# akcel_onlyboard.net
KiCad netlist of a schematic drawn in EAGLE
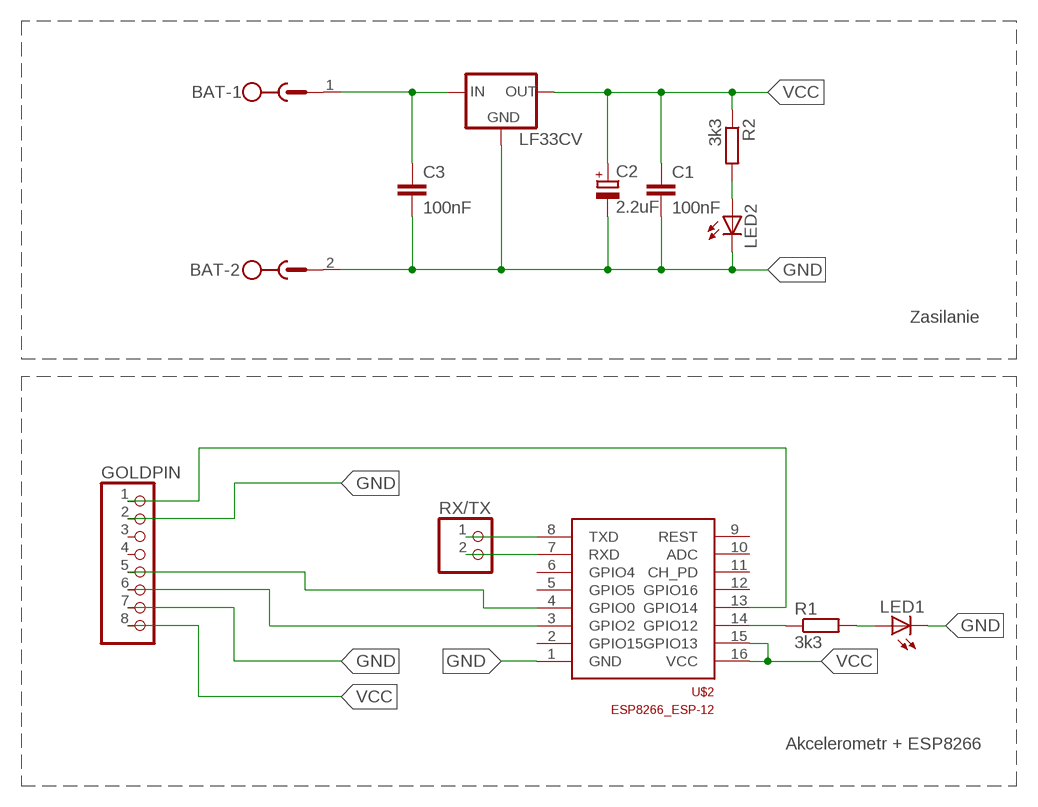
[diagram p0: schematic, sheet 1]

(export (version "E")
  (design (tool "Eeschema 10.0.6"))
  (components
    (comp (ref "BAT")
      (value "MSTBV2")
      (footprint "eagle-import:MSTBV2")
      (libsource (lib "eagle-import") (part "MSTBV2"))
    )
    (comp (ref "C1")
      (value "100nF")
      (footprint "eagle-import:C0805K")
      (libsource (lib "eagle-import") (part "C-EUC0805K"))
    )
    (comp (ref "C2")
      (value "2.2uF")
      (footprint "eagle-import:153CLV-0405")
      (libsource (lib "eagle-import") (part "CPOL-EU153CLV-0405"))
    )
    (comp (ref "C3")
      (value "100nF")
      (footprint "eagle-import:C0805K")
      (libsource (lib "eagle-import") (part "C-EUC0805K"))
    )
    (comp (ref "GOLDPIN")
      (value "PINHD-1X8")
      (footprint "eagle-import:1X08")
      (libsource (lib "eagle-import") (part "PINHD-1X8"))
    )
    (comp (ref "LED1")
      (value "LED3MM")
      (footprint "eagle-import:LED3MM")
      (libsource (lib "eagle-import") (part "LED3MM"))
    )
    (comp (ref "LED2")
      (value "LED3MM")
      (footprint "eagle-import:LED3MM")
      (libsource (lib "eagle-import") (part "LED3MM"))
    )
    (comp (ref "LF33CV")
      (value "LM1117TO252")
      (footprint "eagle-import:TO252")
      (libsource (lib "eagle-import") (part "LM1117TO252"))
    )
    (comp (ref "R1")
      (value "3k3")
      (footprint "eagle-import:M0805")
      (libsource (lib "eagle-import") (part "R-EU_M0805"))
    )
    (comp (ref "R2")
      (value "3k3")
      (footprint "eagle-import:M0805")
      (libsource (lib "eagle-import") (part "R-EU_M0805"))
    )
    (comp (ref "RX/TX")
      (value "PINHD-1X2")
      (footprint "eagle-import:1X02")
      (libsource (lib "eagle-import") (part "PINHD-1X2"))
    )
    (comp (ref "U$2")
      (value "ESP8266_ESP-12")
      (footprint "eagle-import:ESP8266-ESP12")
      (libsource (lib "eagle-import") (part "ESP8266_ESP-12"))
    )
  )
  (nets
    (net (code "1") (name "GND") (class "Default")
      (node (ref "BAT") (pin "2") (pinfunction "SK_2") (pintype "passive"))
      (node (ref "C1") (pin "2") (pinfunction "2_2") (pintype "passive"))
      (node (ref "C2") (pin "-") (pinfunction "-_-") (pintype "passive"))
      (node (ref "C3") (pin "2") (pinfunction "2_2") (pintype "passive"))
      (node (ref "GOLDPIN") (pin "2") (pinfunction "2_2") (pintype "passive"))
      (node (ref "GOLDPIN") (pin "7") (pinfunction "7_7") (pintype "passive"))
      (node (ref "LED1") (pin "K") (pinfunction "C_K") (pintype "passive"))
      (node (ref "LED2") (pin "K") (pinfunction "C_K") (pintype "passive"))
      (node (ref "LF33CV") (pin "3") (pinfunction "GND_3") (pintype "input"))
      (node (ref "U$2") (pin "1") (pinfunction "GND_1") (pintype "bidirectional"))
    )
    (net (code "2") (name "Net-(BATA-SK)") (class "Default")
      (node (ref "BAT") (pin "1") (pinfunction "SK_1") (pintype "passive"))
      (node (ref "C3") (pin "1") (pinfunction "1_1") (pintype "passive"))
      (node (ref "LF33CV") (pin "1") (pinfunction "IN_1") (pintype "input"))
    )
    (net (code "3") (name "Net-(LED1-PadA)") (class "Default")
      (node (ref "LED1") (pin "A") (pinfunction "A_A") (pintype "passive"))
      (node (ref "R1") (pin "2") (pinfunction "2_2") (pintype "passive"))
    )
    (net (code "4") (name "Net-(LED2-PadA)") (class "Default")
      (node (ref "LED2") (pin "A") (pinfunction "A_A") (pintype "passive"))
      (node (ref "R2") (pin "2") (pinfunction "2_2") (pintype "passive"))
    )
    (net (code "5") (name "Net-(U$2-GPIO0)") (class "Default")
      (node (ref "GOLDPIN") (pin "5") (pinfunction "5_5") (pintype "passive"))
      (node (ref "U$2") (pin "4") (pinfunction "GPIO0_4") (pintype "bidirectional"))
    )
    (net (code "6") (name "Net-(U$2-GPIO2)") (class "Default")
      (node (ref "GOLDPIN") (pin "6") (pinfunction "6_6") (pintype "passive"))
      (node (ref "U$2") (pin "3") (pinfunction "GPIO2_3") (pintype "bidirectional"))
    )
    (net (code "7") (name "Net-(U$2-GPIO12)") (class "Default")
      (node (ref "R1") (pin "1") (pinfunction "1_1") (pintype "passive"))
      (node (ref "U$2") (pin "14") (pinfunction "GPIO12_14") (pintype "bidirectional"))
    )
    (net (code "8") (name "Net-(U$2-GPIO14)") (class "Default")
      (node (ref "GOLDPIN") (pin "1") (pinfunction "1_1") (pintype "passive"))
      (node (ref "U$2") (pin "13") (pinfunction "GPIO14_13") (pintype "bidirectional"))
    )
    (net (code "9") (name "Net-(U$2-RXD)") (class "Default")
      (node (ref "RX/TX") (pin "2") (pinfunction "2_2") (pintype "passive"))
      (node (ref "U$2") (pin "7") (pinfunction "RXD_7") (pintype "bidirectional"))
    )
    (net (code "10") (name "Net-(U$2-TXD)") (class "Default")
      (node (ref "RX/TX") (pin "1") (pinfunction "1_1") (pintype "passive"))
      (node (ref "U$2") (pin "8") (pinfunction "TXD_8") (pintype "bidirectional"))
    )
    (net (code "11") (name "VCC") (class "Default")
      (node (ref "C1") (pin "1") (pinfunction "1_1") (pintype "passive"))
      (node (ref "C2") (pin "+") (pinfunction "+_+") (pintype "passive"))
      (node (ref "GOLDPIN") (pin "8") (pinfunction "8_8") (pintype "passive"))
      (node (ref "LF33CV") (pin "2") (pinfunction "OUT_2") (pintype "passive"))
      (node (ref "R2") (pin "1") (pinfunction "1_1") (pintype "passive"))
      (node (ref "U$2") (pin "15") (pinfunction "GPIO13_15") (pintype "bidirectional"))
      (node (ref "U$2") (pin "16") (pinfunction "VCC_16") (pintype "bidirectional"))
    )
    (net (code "12") (name "unconnected-(GOLDPIN-Pad3)") (class "Default")
      (node (ref "GOLDPIN") (pin "3") (pinfunction "3_3") (pintype "passive"))
    )
    (net (code "13") (name "unconnected-(GOLDPIN-Pad4)") (class "Default")
      (node (ref "GOLDPIN") (pin "4") (pinfunction "4_4") (pintype "passive"))
    )
    (net (code "14") (name "unconnected-(U$2-ADC-Pad10)") (class "Default")
      (node (ref "U$2") (pin "10") (pinfunction "ADC_10") (pintype "bidirectional"))
    )
    (net (code "15") (name "unconnected-(U$2-CH_PD-Pad11)") (class "Default")
      (node (ref "U$2") (pin "11") (pinfunction "CH_PD_11") (pintype "bidirectional"))
    )
    (net (code "16") (name "unconnected-(U$2-GPIO4-Pad6)") (class "Default")
      (node (ref "U$2") (pin "6") (pinfunction "GPIO4_6") (pintype "bidirectional"))
    )
    (net (code "17") (name "unconnected-(U$2-GPIO5-Pad5)") (class "Default")
      (node (ref "U$2") (pin "5") (pinfunction "GPIO5_5") (pintype "bidirectional"))
    )
    (net (code "18") (name "unconnected-(U$2-GPIO15-Pad2)") (class "Default")
      (node (ref "U$2") (pin "2") (pinfunction "GPIO15_2") (pintype "bidirectional"))
    )
    (net (code "19") (name "unconnected-(U$2-GPIO16-Pad12)") (class "Default")
      (node (ref "U$2") (pin "12") (pinfunction "GPIO16_12") (pintype "bidirectional"))
    )
    (net (code "20") (name "unconnected-(U$2-REST-Pad9)") (class "Default")
      (node (ref "U$2") (pin "9") (pinfunction "REST_9") (pintype "bidirectional"))
    )
  )
)
